# Top.net
KiCad netlist of a schematic drawn in Altium Designer
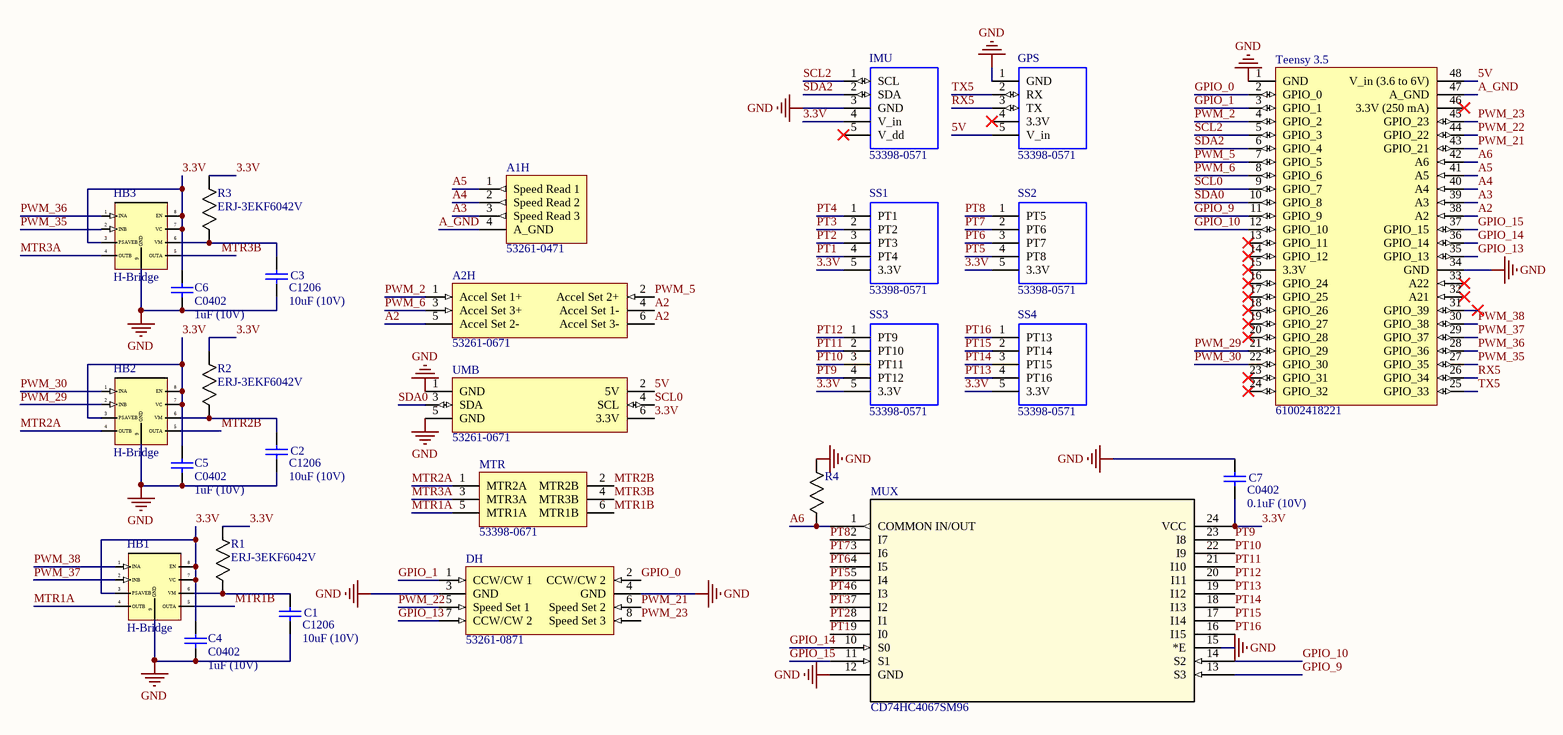
[diagram p0: Top.SchDoc]

(export (version "E")
  (design (tool "Eeschema 10.0.6"))
  (components
    (comp (ref "A1H")
      (value "53261-0471")
      (footprint "53261-0471")
      (fields (field (name "RS PART NUMBER") "5427113P"))
      (libsource (lib "PicoBlade 4POS RA SMD") (part "53261-0471"))
    )
    (comp (ref "A2H")
      (value "53261-0671")
      (footprint "53261-0671")
      (fields (field (name "RS PART NUMBER") "5427135P"))
      (libsource (lib "PicoBlade 6POS RA SMD") (part "53261-0671"))
    )
    (comp (ref "C1")
      (value "C1206")
      (footprint "CC1206N")
      (description "Ceramic Chip Capacitor - Standard")
      (fields (field (name "ALTIUM_VALUE") "10uF (10V)") (field (name "PUBLISHER") "Altium Limited"))
      (libsource (lib "KEMET Chip Capacitor") (part "C1206"))
    )
    (comp (ref "C2")
      (value "C1206")
      (footprint "CC1206N")
      (description "Ceramic Chip Capacitor - Standard")
      (fields (field (name "ALTIUM_VALUE") "10uF (10V)") (field (name "PUBLISHER") "Altium Limited"))
      (libsource (lib "KEMET Chip Capacitor") (part "C1206"))
    )
    (comp (ref "C3")
      (value "C1206")
      (footprint "CC1206N")
      (description "Ceramic Chip Capacitor - Standard")
      (fields (field (name "ALTIUM_VALUE") "10uF (10V)") (field (name "PUBLISHER") "Altium Limited"))
      (libsource (lib "KEMET Chip Capacitor") (part "C1206"))
    )
    (comp (ref "C4")
      (value "C0402")
      (footprint "CC1206N")
      (description "Ceramic Chip Capacitor - Standard")
      (fields (field (name "ALTIUM_VALUE") "1uF (10V)") (field (name "PUBLISHER") "Altium Limited"))
      (libsource (lib "KEMET Chip Capacitor") (part "C0402"))
    )
    (comp (ref "C5")
      (value "C0402")
      (footprint "CC1206N")
      (description "Ceramic Chip Capacitor - Standard")
      (fields (field (name "ALTIUM_VALUE") "1uF (10V)") (field (name "PUBLISHER") "Altium Limited"))
      (libsource (lib "KEMET Chip Capacitor") (part "C0402"))
    )
    (comp (ref "C6")
      (value "C0402")
      (footprint "CC1206N")
      (description "Ceramic Chip Capacitor - Standard")
      (fields (field (name "ALTIUM_VALUE") "1uF (10V)") (field (name "PUBLISHER") "Altium Limited"))
      (libsource (lib "KEMET Chip Capacitor") (part "C0402"))
    )
    (comp (ref "C7")
      (value "C0402")
      (footprint "CC1206N")
      (description "Ceramic Chip Capacitor - Standard")
      (fields (field (name "ALTIUM_VALUE") "0.1uF (10V)") (field (name "PUBLISHER") "Altium Limited"))
      (libsource (lib "KEMET Chip Capacitor") (part "C0402"))
    )
    (comp (ref "DH")
      (value "53261-0871")
      (footprint "53261-0871")
      (fields (field (name "RS PART NUMBER") "5427157P"))
      (libsource (lib "Picoblade 8POS RA SMD") (part "53261-0871"))
    )
    (comp (ref "GPS")
      (value "53398-0571")
      (footprint "53398-0571")
      (fields (field (name "RS PART NUMBER") "5427292"))
      (libsource (lib "PicoBlade 5POS VERT SMD") (part "53398-0571"))
    )
    (comp (ref "HB1")
      (value "H-Bridge")
      (footprint "AP1017")
      (libsource (lib "SchematicComponents") (part "AP1017AEN"))
    )
    (comp (ref "HB2")
      (value "H-Bridge")
      (footprint "AP1017")
      (libsource (lib "SchematicComponents") (part "AP1017AEN"))
    )
    (comp (ref "HB3")
      (value "H-Bridge")
      (footprint "AP1017")
      (libsource (lib "SchematicComponents") (part "AP1017AEN"))
    )
    (comp (ref "IMU")
      (value "53398-0571")
      (footprint "53398-0571")
      (fields (field (name "RS PART NUMBER") "5427292"))
      (libsource (lib "PicoBlade 5POS VERT SMD") (part "53398-0571"))
    )
    (comp (ref "MTR")
      (value "53398-0671")
      (footprint "533980671")
      (fields (field (name "RS PART NUMBER") "5427214P"))
      (libsource (lib "53398-0671") (part "53398-0671"))
    )
    (comp (ref "MUX")
      (value "CD74HC4067SM96")
      (footprint "CD74HC4067SM96")
      (libsource (lib "SchematicComponents") (part "CD74HC4067SM96"))
    )
    (comp (ref "R1")
      (value "ERJ-3EKF6042V")
      (footprint "RC0603N")
      (description "Imported")
      (libsource (lib "60 Ohm Resistor, ERJ-3EKF6042V") (part "ERJ-3EKF6042V"))
    )
    (comp (ref "R2")
      (value "ERJ-3EKF6042V")
      (footprint "RC0603N")
      (description "Imported")
      (libsource (lib "60 Ohm Resistor, ERJ-3EKF6042V") (part "ERJ-3EKF6042V"))
    )
    (comp (ref "R3")
      (value "ERJ-3EKF6042V")
      (footprint "RC0603N")
      (description "Imported")
      (libsource (lib "60 Ohm Resistor, ERJ-3EKF6042V") (part "ERJ-3EKF6042V"))
    )
    (comp (ref "R4")
      (value "~")
      (footprint "RC0603N")
      (description "Imported")
      (fields (field (name "MANUFACTURER_PART_NUMBER") "ERJ-3EKF6042V"))
      (libsource (lib "60 Ohm Resistor, ERJ-3EKF6042V") (part "ERJ-3EKF6042V"))
    )
    (comp (ref "SS1")
      (value "53398-0571")
      (footprint "53398-0571")
      (fields (field (name "RS PART NUMBER") "5427292"))
      (libsource (lib "PicoBlade 5POS VERT SMD") (part "53398-0571"))
    )
    (comp (ref "SS2")
      (value "53398-0571")
      (footprint "53398-0571")
      (fields (field (name "RS PART NUMBER") "5427292"))
      (libsource (lib "PicoBlade 5POS VERT SMD") (part "53398-0571"))
    )
    (comp (ref "SS3")
      (value "53398-0571")
      (footprint "53398-0571")
      (fields (field (name "RS PART NUMBER") "5427292"))
      (libsource (lib "PicoBlade 5POS VERT SMD") (part "53398-0571"))
    )
    (comp (ref "SS4")
      (value "53398-0571")
      (footprint "53398-0571")
      (fields (field (name "RS PART NUMBER") "5427292"))
      (libsource (lib "PicoBlade 5POS VERT SMD") (part "53398-0571"))
    )
    (comp (ref "Teensy 3.5")
      (value "61002418221")
      (footprint "61002418221")
      (fields (field (name "RS PART NUMBER") "1216841"))
      (libsource (lib "Teensy 3-5 24POS 2ROW SMD") (part "61002418221"))
    )
    (comp (ref "UMB")
      (value "53261-0671")
      (footprint "53261-0671")
      (fields (field (name "RS PART NUMBER") "5427135P"))
      (libsource (lib "PicoBlade 6POS RA SMD") (part "53261-0671"))
    )
  )
  (nets
    (net (code "1") (name "/3.3V") (class "Default")
      (node (ref "C4") (pin "2") (pinfunction "2_2") (pintype "passive"))
      (node (ref "C5") (pin "2") (pinfunction "2_2") (pintype "passive"))
      (node (ref "C6") (pin "2") (pinfunction "2_2") (pintype "passive"))
      (node (ref "C7") (pin "1") (pinfunction "1_1") (pintype "passive"))
      (node (ref "HB1") (pin "3") (pinfunction "PSAVEB_3") (pintype "power_in"))
      (node (ref "HB1") (pin "7") (pinfunction "VC_7") (pintype "power_in"))
      (node (ref "HB1") (pin "8") (pinfunction "EN_8") (pintype "power_in"))
      (node (ref "HB2") (pin "3") (pinfunction "PSAVEB_3") (pintype "power_in"))
      (node (ref "HB2") (pin "7") (pinfunction "VC_7") (pintype "power_in"))
      (node (ref "HB2") (pin "8") (pinfunction "EN_8") (pintype "power_in"))
      (node (ref "HB3") (pin "3") (pinfunction "PSAVEB_3") (pintype "power_in"))
      (node (ref "HB3") (pin "7") (pinfunction "VC_7") (pintype "power_in"))
      (node (ref "HB3") (pin "8") (pinfunction "EN_8") (pintype "power_in"))
      (node (ref "IMU") (pin "4") (pinfunction "PT12_4") (pintype "passive"))
      (node (ref "MUX") (pin "24") (pinfunction "VCC_24") (pintype "power_in"))
      (node (ref "R1") (pin "1") (pinfunction "1_1") (pintype "passive"))
      (node (ref "R2") (pin "1") (pinfunction "1_1") (pintype "passive"))
      (node (ref "R3") (pin "1") (pinfunction "1_1") (pintype "passive"))
      (node (ref "SS1") (pin "5") (pinfunction "3.3V_5") (pintype "power_in"))
      (node (ref "SS2") (pin "5") (pinfunction "3.3V_5") (pintype "power_in"))
      (node (ref "SS3") (pin "5") (pinfunction "3.3V_5") (pintype "power_in"))
      (node (ref "SS4") (pin "5") (pinfunction "3.3V_5") (pintype "power_in"))
      (node (ref "UMB") (pin "6") (pinfunction "3.3V_6") (pintype "power_in"))
    )
    (net (code "2") (name "/5V") (class "Default")
      (node (ref "GPS") (pin "5") (pinfunction "3.3V_5") (pintype "power_in"))
      (node (ref "Teensy 3.5") (pin "48") (pinfunction "V_in_(3.6_to_6V)_48") (pintype "power_in"))
      (node (ref "UMB") (pin "2") (pinfunction "5V_2") (pintype "power_in"))
    )
    (net (code "3") (name "/A2") (class "Default")
      (node (ref "A2H") (pin "4") (pinfunction "SCL_4") (pintype "bidirectional"))
      (node (ref "A2H") (pin "5") (pinfunction "GND_5") (pintype "power_in"))
      (node (ref "A2H") (pin "6") (pinfunction "3.3V_6") (pintype "power_in"))
      (node (ref "Teensy 3.5") (pin "38") (pinfunction "A2_38") (pintype "input"))
    )
    (net (code "4") (name "/A3") (class "Default")
      (node (ref "A1H") (pin "3") (pinfunction "Speed_Read_3_3") (pintype "output"))
      (node (ref "Teensy 3.5") (pin "39") (pinfunction "A3_39") (pintype "input"))
    )
    (net (code "5") (name "/A4") (class "Default")
      (node (ref "A1H") (pin "2") (pinfunction "Speed_Read_2_2") (pintype "output"))
      (node (ref "Teensy 3.5") (pin "40") (pinfunction "A4_40") (pintype "input"))
    )
    (net (code "6") (name "/A5") (class "Default")
      (node (ref "A1H") (pin "1") (pinfunction "Speed_Read_1_1") (pintype "output"))
      (node (ref "Teensy 3.5") (pin "41") (pinfunction "A5_41") (pintype "input"))
    )
    (net (code "7") (name "/A6") (class "Default")
      (node (ref "MUX") (pin "1") (pinfunction "COMMON_IN/OUT_1") (pintype "output"))
      (node (ref "R4") (pin "2") (pinfunction "2_2") (pintype "passive"))
      (node (ref "Teensy 3.5") (pin "42") (pinfunction "A6_42") (pintype "input"))
    )
    (net (code "8") (name "/A_GND") (class "Default")
      (node (ref "A1H") (pin "4") (pinfunction "A_GND_4") (pintype "power_in"))
      (node (ref "Teensy 3.5") (pin "47") (pinfunction "A_GND_47") (pintype "power_in"))
    )
    (net (code "9") (name "/GPIO_0") (class "Default")
      (node (ref "DH") (pin "2") (pinfunction "CCW/CW_2_2") (pintype "input"))
      (node (ref "Teensy 3.5") (pin "2") (pinfunction "GPIO_0_2") (pintype "bidirectional"))
    )
    (net (code "10") (name "/GPIO_1") (class "Default")
      (node (ref "DH") (pin "1") (pinfunction "CCW/CW_1_1") (pintype "input"))
      (node (ref "Teensy 3.5") (pin "3") (pinfunction "GPIO_1_3") (pintype "bidirectional"))
    )
    (net (code "11") (name "/GPIO_9") (class "Default")
      (node (ref "MUX") (pin "13") (pinfunction "S3_13") (pintype "input"))
      (node (ref "Teensy 3.5") (pin "11") (pinfunction "GPIO_9_11") (pintype "bidirectional"))
    )
    (net (code "12") (name "/GPIO_10") (class "Default")
      (node (ref "MUX") (pin "14") (pinfunction "S2_14") (pintype "input"))
      (node (ref "Teensy 3.5") (pin "12") (pinfunction "GPIO_10_12") (pintype "bidirectional"))
    )
    (net (code "13") (name "/GPIO_13") (class "Default")
      (node (ref "DH") (pin "7") (pinfunction "CCW/CW_2_7") (pintype "input"))
      (node (ref "Teensy 3.5") (pin "35") (pinfunction "GPIO_13_35") (pintype "bidirectional"))
    )
    (net (code "14") (name "/GPIO_14") (class "Default")
      (node (ref "MUX") (pin "10") (pinfunction "S0_10") (pintype "input"))
      (node (ref "Teensy 3.5") (pin "36") (pinfunction "GPIO_14_36") (pintype "bidirectional"))
    )
    (net (code "15") (name "/GPIO_15") (class "Default")
      (node (ref "MUX") (pin "11") (pinfunction "S1_11") (pintype "input"))
      (node (ref "Teensy 3.5") (pin "37") (pinfunction "GPIO_15_37") (pintype "bidirectional"))
    )
    (net (code "16") (name "/MTR1A") (class "Default")
      (node (ref "HB1") (pin "4") (pinfunction "OUTB_4") (pintype "power_in"))
      (node (ref "MTR") (pin "5") (pinfunction "MTR1A_5") (pintype "power_in"))
    )
    (net (code "17") (name "/MTR1B") (class "Default")
      (node (ref "HB1") (pin "5") (pinfunction "OUTA_5") (pintype "power_in"))
      (node (ref "MTR") (pin "6") (pinfunction "MTR1B_6") (pintype "power_in"))
    )
    (net (code "18") (name "/MTR2A") (class "Default")
      (node (ref "HB2") (pin "4") (pinfunction "OUTB_4") (pintype "power_in"))
      (node (ref "MTR") (pin "1") (pinfunction "MTR2A_1") (pintype "power_in"))
    )
    (net (code "19") (name "/MTR2B") (class "Default")
      (node (ref "HB2") (pin "5") (pinfunction "OUTA_5") (pintype "power_in"))
      (node (ref "MTR") (pin "2") (pinfunction "MTR2B_2") (pintype "power_in"))
    )
    (net (code "20") (name "/MTR3A") (class "Default")
      (node (ref "HB3") (pin "4") (pinfunction "OUTB_4") (pintype "power_in"))
      (node (ref "MTR") (pin "3") (pinfunction "MTR3A_3") (pintype "power_in"))
    )
    (net (code "21") (name "/MTR3B") (class "Default")
      (node (ref "HB3") (pin "5") (pinfunction "OUTA_5") (pintype "power_in"))
      (node (ref "MTR") (pin "4") (pinfunction "MTR3B_4") (pintype "power_in"))
    )
    (net (code "22") (name "/PT1") (class "Default")
      (node (ref "MUX") (pin "9") (pinfunction "I0_9") (pintype "passive"))
      (node (ref "SS1") (pin "4") (pinfunction "PT12_4") (pintype "passive"))
    )
    (net (code "23") (name "/PT2") (class "Default")
      (node (ref "MUX") (pin "8") (pinfunction "I1_8") (pintype "passive"))
      (node (ref "SS1") (pin "3") (pinfunction "PT11_3") (pintype "passive"))
    )
    (net (code "24") (name "/PT3") (class "Default")
      (node (ref "MUX") (pin "7") (pinfunction "I2_7") (pintype "passive"))
      (node (ref "SS1") (pin "2") (pinfunction "PT10_2") (pintype "passive"))
    )
    (net (code "25") (name "/PT4") (class "Default")
      (node (ref "MUX") (pin "6") (pinfunction "I3_6") (pintype "passive"))
      (node (ref "SS1") (pin "1") (pinfunction "PT9_1") (pintype "passive"))
    )
    (net (code "26") (name "/PT5") (class "Default")
      (node (ref "MUX") (pin "5") (pinfunction "I4_5") (pintype "passive"))
      (node (ref "SS2") (pin "4") (pinfunction "PT12_4") (pintype "passive"))
    )
    (net (code "27") (name "/PT6") (class "Default")
      (node (ref "MUX") (pin "4") (pinfunction "I5_4") (pintype "passive"))
      (node (ref "SS2") (pin "3") (pinfunction "PT11_3") (pintype "passive"))
    )
    (net (code "28") (name "/PT7") (class "Default")
      (node (ref "MUX") (pin "3") (pinfunction "I6_3") (pintype "passive"))
      (node (ref "SS2") (pin "2") (pinfunction "PT10_2") (pintype "passive"))
    )
    (net (code "29") (name "/PT8") (class "Default")
      (node (ref "MUX") (pin "2") (pinfunction "I7_2") (pintype "passive"))
      (node (ref "SS2") (pin "1") (pinfunction "PT9_1") (pintype "passive"))
    )
    (net (code "30") (name "/PT9") (class "Default")
      (node (ref "MUX") (pin "23") (pinfunction "I8_23") (pintype "passive"))
      (node (ref "SS3") (pin "4") (pinfunction "PT12_4") (pintype "passive"))
    )
    (net (code "31") (name "/PT10") (class "Default")
      (node (ref "MUX") (pin "22") (pinfunction "I9_22") (pintype "passive"))
      (node (ref "SS3") (pin "3") (pinfunction "PT11_3") (pintype "passive"))
    )
    (net (code "32") (name "/PT11") (class "Default")
      (node (ref "MUX") (pin "21") (pinfunction "I10_21") (pintype "passive"))
      (node (ref "SS3") (pin "2") (pinfunction "PT10_2") (pintype "passive"))
    )
    (net (code "33") (name "/PT12") (class "Default")
      (node (ref "MUX") (pin "20") (pinfunction "I11_20") (pintype "passive"))
      (node (ref "SS3") (pin "1") (pinfunction "PT9_1") (pintype "passive"))
    )
    (net (code "34") (name "/PT13") (class "Default")
      (node (ref "MUX") (pin "19") (pinfunction "I12_19") (pintype "passive"))
      (node (ref "SS4") (pin "4") (pinfunction "PT12_4") (pintype "passive"))
    )
    (net (code "35") (name "/PT14") (class "Default")
      (node (ref "MUX") (pin "18") (pinfunction "I13_18") (pintype "passive"))
      (node (ref "SS4") (pin "3") (pinfunction "PT11_3") (pintype "passive"))
    )
    (net (code "36") (name "/PT15") (class "Default")
      (node (ref "MUX") (pin "17") (pinfunction "I14_17") (pintype "passive"))
      (node (ref "SS4") (pin "2") (pinfunction "PT10_2") (pintype "passive"))
    )
    (net (code "37") (name "/PT16") (class "Default")
      (node (ref "MUX") (pin "16") (pinfunction "I15_16") (pintype "passive"))
      (node (ref "SS4") (pin "1") (pinfunction "PT9_1") (pintype "passive"))
    )
    (net (code "38") (name "/PWM_2") (class "Default")
      (node (ref "A2H") (pin "1") (pinfunction "GND_1") (pintype "power_in"))
      (node (ref "Teensy 3.5") (pin "4") (pinfunction "GPIO_2_4") (pintype "bidirectional"))
    )
    (net (code "39") (name "/PWM_5") (class "Default")
      (node (ref "A2H") (pin "2") (pinfunction "5V_2") (pintype "power_in"))
      (node (ref "Teensy 3.5") (pin "7") (pinfunction "GPIO_5_7") (pintype "bidirectional"))
    )
    (net (code "40") (name "/PWM_6") (class "Default")
      (node (ref "A2H") (pin "3") (pinfunction "SDA_3") (pintype "bidirectional"))
      (node (ref "Teensy 3.5") (pin "8") (pinfunction "GPIO_6_8") (pintype "bidirectional"))
    )
    (net (code "41") (name "/PWM_21") (class "Default")
      (node (ref "DH") (pin "6") (pinfunction "Speed_Set_2_6") (pintype "input"))
      (node (ref "Teensy 3.5") (pin "43") (pinfunction "GPIO_21_43") (pintype "bidirectional"))
    )
    (net (code "42") (name "/PWM_22") (class "Default")
      (node (ref "DH") (pin "5") (pinfunction "Speed_Set_1_5") (pintype "input"))
      (node (ref "Teensy 3.5") (pin "44") (pinfunction "GPIO_22_44") (pintype "bidirectional"))
    )
    (net (code "43") (name "/PWM_23") (class "Default")
      (node (ref "DH") (pin "8") (pinfunction "Speed_Set_3_8") (pintype "input"))
      (node (ref "Teensy 3.5") (pin "45") (pinfunction "GPIO_23_45") (pintype "bidirectional"))
    )
    (net (code "44") (name "/PWM_29") (class "Default")
      (node (ref "HB2") (pin "2") (pinfunction "INB_2") (pintype "input"))
      (node (ref "Teensy 3.5") (pin "21") (pinfunction "GPIO_29_21") (pintype "bidirectional"))
    )
    (net (code "45") (name "/PWM_30") (class "Default")
      (node (ref "HB2") (pin "1") (pinfunction "INA_1") (pintype "input"))
      (node (ref "Teensy 3.5") (pin "22") (pinfunction "GPIO_30_22") (pintype "bidirectional"))
    )
    (net (code "46") (name "/PWM_35") (class "Default")
      (node (ref "HB3") (pin "2") (pinfunction "INB_2") (pintype "input"))
      (node (ref "Teensy 3.5") (pin "27") (pinfunction "GPIO_35_27") (pintype "bidirectional"))
    )
    (net (code "47") (name "/PWM_36") (class "Default")
      (node (ref "HB3") (pin "1") (pinfunction "INA_1") (pintype "input"))
      (node (ref "Teensy 3.5") (pin "28") (pinfunction "GPIO_36_28") (pintype "bidirectional"))
    )
    (net (code "48") (name "/PWM_37") (class "Default")
      (node (ref "HB1") (pin "2") (pinfunction "INB_2") (pintype "input"))
      (node (ref "Teensy 3.5") (pin "29") (pinfunction "GPIO_37_29") (pintype "bidirectional"))
    )
    (net (code "49") (name "/PWM_38") (class "Default")
      (node (ref "HB1") (pin "1") (pinfunction "INA_1") (pintype "input"))
      (node (ref "Teensy 3.5") (pin "30") (pinfunction "GPIO_38_30") (pintype "bidirectional"))
    )
    (net (code "50") (name "/RX5") (class "Default")
      (node (ref "GPS") (pin "3") (pinfunction "PT11_3") (pintype "passive"))
      (node (ref "Teensy 3.5") (pin "26") (pinfunction "GPIO_34_26") (pintype "bidirectional"))
    )
    (net (code "51") (name "/SCL0") (class "Default")
      (node (ref "Teensy 3.5") (pin "9") (pinfunction "GPIO_7_9") (pintype "bidirectional"))
      (node (ref "UMB") (pin "4") (pinfunction "SCL_4") (pintype "bidirectional"))
    )
    (net (code "52") (name "/SCL2") (class "Default")
      (node (ref "IMU") (pin "1") (pinfunction "PT9_1") (pintype "passive"))
      (node (ref "Teensy 3.5") (pin "5") (pinfunction "GPIO_3_5") (pintype "bidirectional"))
    )
    (net (code "53") (name "/SDA0") (class "Default")
      (node (ref "Teensy 3.5") (pin "10") (pinfunction "GPIO_8_10") (pintype "bidirectional"))
      (node (ref "UMB") (pin "3") (pinfunction "SDA_3") (pintype "bidirectional"))
    )
    (net (code "54") (name "/SDA2") (class "Default")
      (node (ref "IMU") (pin "2") (pinfunction "PT10_2") (pintype "passive"))
      (node (ref "Teensy 3.5") (pin "6") (pinfunction "GPIO_4_6") (pintype "bidirectional"))
    )
    (net (code "55") (name "/TX5") (class "Default")
      (node (ref "GPS") (pin "2") (pinfunction "PT10_2") (pintype "passive"))
      (node (ref "Teensy 3.5") (pin "25") (pinfunction "GPIO_33_25") (pintype "bidirectional"))
    )
    (net (code "56") (name "GND") (class "Default")
      (node (ref "C1") (pin "1") (pinfunction "1_1") (pintype "passive"))
      (node (ref "C2") (pin "1") (pinfunction "1_1") (pintype "passive"))
      (node (ref "C3") (pin "1") (pinfunction "1_1") (pintype "passive"))
      (node (ref "C4") (pin "1") (pinfunction "1_1") (pintype "passive"))
      (node (ref "C5") (pin "1") (pinfunction "1_1") (pintype "passive"))
      (node (ref "C6") (pin "1") (pinfunction "1_1") (pintype "passive"))
      (node (ref "C7") (pin "2") (pinfunction "2_2") (pintype "passive"))
      (node (ref "DH") (pin "3") (pinfunction "GND_3") (pintype "power_in"))
      (node (ref "DH") (pin "4") (pinfunction "GND_4") (pintype "power_in"))
      (node (ref "GPS") (pin "1") (pinfunction "PT9_1") (pintype "passive"))
      (node (ref "HB1") (pin "9") (pinfunction "GND_9") (pintype "power_in"))
      (node (ref "HB2") (pin "9") (pinfunction "GND_9") (pintype "power_in"))
      (node (ref "HB3") (pin "9") (pinfunction "GND_9") (pintype "power_in"))
      (node (ref "IMU") (pin "3") (pinfunction "PT11_3") (pintype "passive"))
      (node (ref "MUX") (pin "12") (pinfunction "GND_12") (pintype "power_in"))
      (node (ref "MUX") (pin "15") (pinfunction "*E_15") (pintype "passive"))
      (node (ref "R4") (pin "1") (pinfunction "1_1") (pintype "passive"))
      (node (ref "Teensy 3.5") (pin "1") (pinfunction "GND_1") (pintype "power_in"))
      (node (ref "Teensy 3.5") (pin "34") (pinfunction "GND_34") (pintype "power_in"))
      (node (ref "UMB") (pin "1") (pinfunction "GND_1") (pintype "power_in"))
      (node (ref "UMB") (pin "5") (pinfunction "GND_5") (pintype "power_in"))
    )
    (net (code "57") (name "Net-(HB1-VM)") (class "Default")
      (node (ref "C1") (pin "2") (pinfunction "2_2") (pintype "passive"))
      (node (ref "HB1") (pin "6") (pinfunction "VM_6") (pintype "power_in"))
      (node (ref "R1") (pin "2") (pinfunction "2_2") (pintype "passive"))
    )
    (net (code "58") (name "Net-(HB2-VM)") (class "Default")
      (node (ref "C2") (pin "2") (pinfunction "2_2") (pintype "passive"))
      (node (ref "HB2") (pin "6") (pinfunction "VM_6") (pintype "power_in"))
      (node (ref "R2") (pin "2") (pinfunction "2_2") (pintype "passive"))
    )
    (net (code "59") (name "Net-(HB3-VM)") (class "Default")
      (node (ref "C3") (pin "2") (pinfunction "2_2") (pintype "passive"))
      (node (ref "HB3") (pin "6") (pinfunction "VM_6") (pintype "power_in"))
      (node (ref "R3") (pin "2") (pinfunction "2_2") (pintype "passive"))
    )
    (net (code "60") (name "unconnected-(GPS-PT12-Pad4)") (class "Default")
      (node (ref "GPS") (pin "4") (pinfunction "PT12_4") (pintype "passive+no_connect"))
    )
    (net (code "61") (name "unconnected-(IMU-3.3V-Pad5)") (class "Default")
      (node (ref "IMU") (pin "5") (pinfunction "3.3V_5") (pintype "power_in+no_connect"))
    )
    (net (code "62") (name "unconnected-(Teensy 3.5-3.3V-Pad15)") (class "Default")
      (node (ref "Teensy 3.5") (pin "15") (pinfunction "3.3V_15") (pintype "power_in+no_connect"))
    )
    (net (code "63") (name "unconnected-(Teensy 3.5-3.3V_(250_mA)-Pad46)") (class "Default")
      (node (ref "Teensy 3.5") (pin "46") (pinfunction "3.3V_(250_mA)_46") (pintype "power_in+no_connect"))
    )
    (net (code "64") (name "unconnected-(Teensy 3.5-A21-Pad32)") (class "Default")
      (node (ref "Teensy 3.5") (pin "32") (pinfunction "A21_32") (pintype "input+no_connect"))
    )
    (net (code "65") (name "unconnected-(Teensy 3.5-A22-Pad33)") (class "Default")
      (node (ref "Teensy 3.5") (pin "33") (pinfunction "A22_33") (pintype "input+no_connect"))
    )
    (net (code "66") (name "unconnected-(Teensy 3.5-GPIO_11-Pad13)") (class "Default")
      (node (ref "Teensy 3.5") (pin "13") (pinfunction "GPIO_11_13") (pintype "bidirectional+no_connect"))
    )
    (net (code "67") (name "unconnected-(Teensy 3.5-GPIO_12-Pad14)") (class "Default")
      (node (ref "Teensy 3.5") (pin "14") (pinfunction "GPIO_12_14") (pintype "bidirectional+no_connect"))
    )
    (net (code "68") (name "unconnected-(Teensy 3.5-GPIO_24-Pad16)") (class "Default")
      (node (ref "Teensy 3.5") (pin "16") (pinfunction "GPIO_24_16") (pintype "bidirectional+no_connect"))
    )
    (net (code "69") (name "unconnected-(Teensy 3.5-GPIO_25-Pad17)") (class "Default")
      (node (ref "Teensy 3.5") (pin "17") (pinfunction "GPIO_25_17") (pintype "bidirectional+no_connect"))
    )
    (net (code "70") (name "unconnected-(Teensy 3.5-GPIO_26-Pad18)") (class "Default")
      (node (ref "Teensy 3.5") (pin "18") (pinfunction "GPIO_26_18") (pintype "bidirectional+no_connect"))
    )
    (net (code "71") (name "unconnected-(Teensy 3.5-GPIO_27-Pad19)") (class "Default")
      (node (ref "Teensy 3.5") (pin "19") (pinfunction "GPIO_27_19") (pintype "bidirectional+no_connect"))
    )
    (net (code "72") (name "unconnected-(Teensy 3.5-GPIO_28-Pad20)") (class "Default")
      (node (ref "Teensy 3.5") (pin "20") (pinfunction "GPIO_28_20") (pintype "bidirectional+no_connect"))
    )
    (net (code "73") (name "unconnected-(Teensy 3.5-GPIO_31-Pad23)") (class "Default")
      (node (ref "Teensy 3.5") (pin "23") (pinfunction "GPIO_31_23") (pintype "bidirectional+no_connect"))
    )
    (net (code "74") (name "unconnected-(Teensy 3.5-GPIO_32-Pad24)") (class "Default")
      (node (ref "Teensy 3.5") (pin "24") (pinfunction "GPIO_32_24") (pintype "bidirectional+no_connect"))
    )
    (net (code "75") (name "unconnected-(Teensy 3.5-GPIO_39-Pad31)") (class "Default")
      (node (ref "Teensy 3.5") (pin "31") (pinfunction "GPIO_39_31") (pintype "bidirectional+no_connect"))
    )
  )
)
